# Acc_v0_1.net
KiCad netlist of a schematic drawn in EAGLE
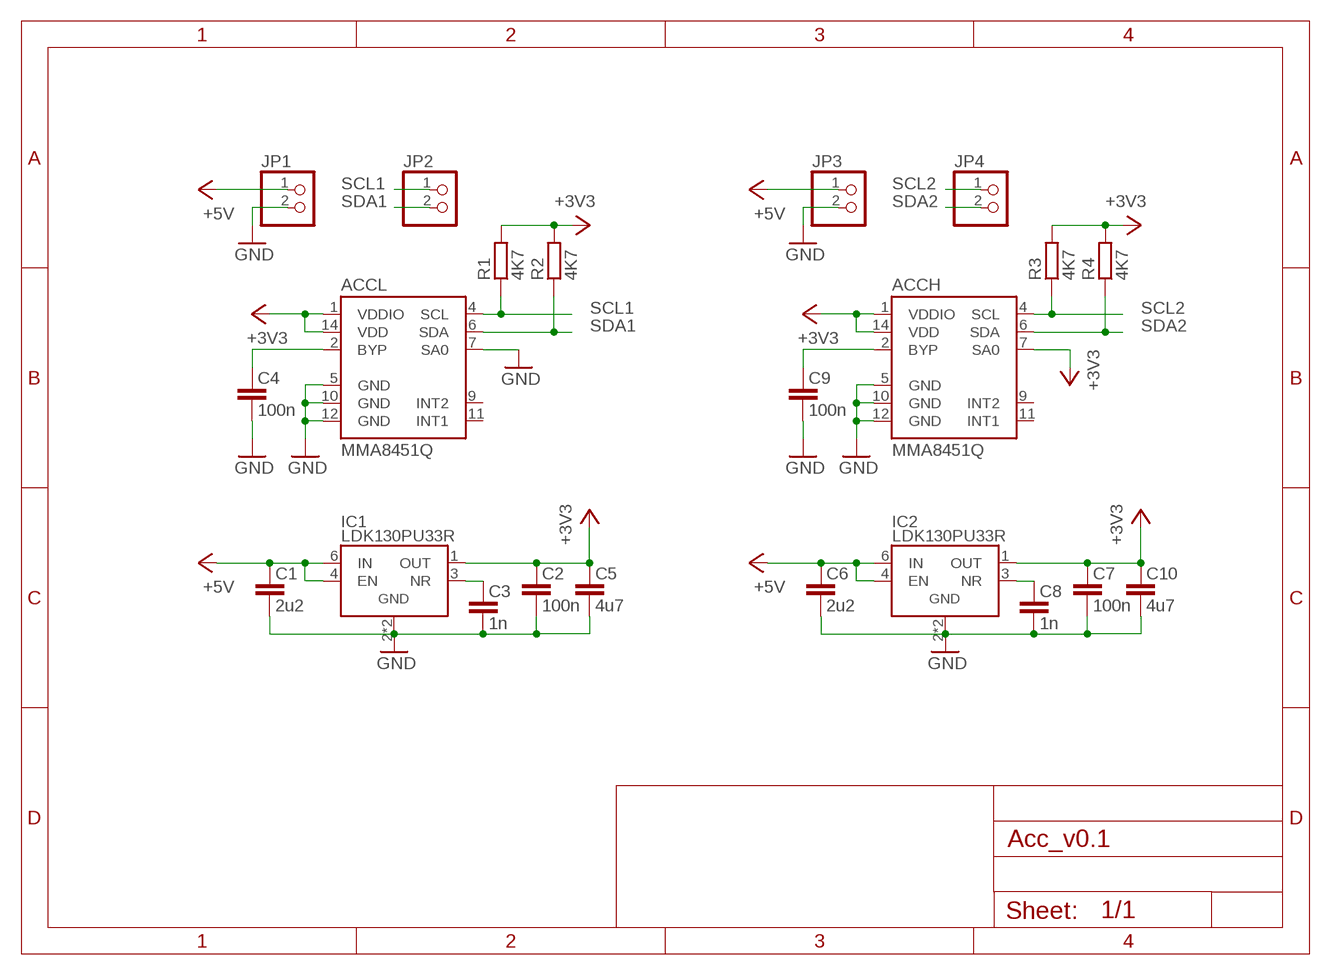
[diagram p0: schematic, sheet 1]

(export (version "E")
  (design (tool "Eeschema 10.0.6"))
  (components
    (comp (ref "ACCH")
      (value "MMA8451Q")
      (footprint "eagle-import:QFN-16")
      (libsource (lib "eagle-import") (part "MMA8451Q"))
    )
    (comp (ref "ACCL")
      (value "MMA8451Q")
      (footprint "eagle-import:QFN-16")
      (libsource (lib "eagle-import") (part "MMA8451Q"))
    )
    (comp (ref "C1")
      (value "2u2")
      (footprint "eagle-import:C0603G")
      (libsource (lib "eagle-import") (part "C_EU_C0603G"))
    )
    (comp (ref "C2")
      (value "100n")
      (footprint "eagle-import:C0603G")
      (libsource (lib "eagle-import") (part "C_EU_C0603G"))
    )
    (comp (ref "C3")
      (value "1n")
      (footprint "eagle-import:C0603G")
      (libsource (lib "eagle-import") (part "C_EU_C0603G"))
    )
    (comp (ref "C4")
      (value "100n")
      (footprint "eagle-import:C0603G")
      (libsource (lib "eagle-import") (part "C_EU_C0603G"))
    )
    (comp (ref "C5")
      (value "4u7")
      (footprint "eagle-import:C0603G")
      (libsource (lib "eagle-import") (part "C_EU_C0603G"))
    )
    (comp (ref "C6")
      (value "2u2")
      (footprint "eagle-import:C0603G")
      (libsource (lib "eagle-import") (part "C_EU_C0603G"))
    )
    (comp (ref "C7")
      (value "100n")
      (footprint "eagle-import:C0603G")
      (libsource (lib "eagle-import") (part "C_EU_C0603G"))
    )
    (comp (ref "C8")
      (value "1n")
      (footprint "eagle-import:C0603G")
      (libsource (lib "eagle-import") (part "C_EU_C0603G"))
    )
    (comp (ref "C9")
      (value "100n")
      (footprint "eagle-import:C0603G")
      (libsource (lib "eagle-import") (part "C_EU_C0603G"))
    )
    (comp (ref "C10")
      (value "4u7")
      (footprint "eagle-import:C0603G")
      (libsource (lib "eagle-import") (part "C_EU_C0603G"))
    )
    (comp (ref "IC1")
      (value "LDK130PU33R")
      (footprint "eagle-import:DFN6L")
      (libsource (lib "eagle-import") (part "LDK130PU33R"))
    )
    (comp (ref "IC2")
      (value "LDK130PU33R")
      (footprint "eagle-import:DFN6L")
      (libsource (lib "eagle-import") (part "LDK130PU33R"))
    )
    (comp (ref "JP1")
      (value "PINHD-1X2/SMD")
      (footprint "eagle-import:1X02S")
      (libsource (lib "eagle-import") (part "PINHD-1X2/SMD"))
    )
    (comp (ref "JP2")
      (value "PINHD-1X2/SMD")
      (footprint "eagle-import:1X02S")
      (libsource (lib "eagle-import") (part "PINHD-1X2/SMD"))
    )
    (comp (ref "JP3")
      (value "PINHD-1X2/SMD")
      (footprint "eagle-import:1X02S")
      (libsource (lib "eagle-import") (part "PINHD-1X2/SMD"))
    )
    (comp (ref "JP4")
      (value "PINHD-1X2/SMD")
      (footprint "eagle-import:1X02S")
      (libsource (lib "eagle-import") (part "PINHD-1X2/SMD"))
    )
    (comp (ref "R1")
      (value "4K7")
      (footprint "eagle-import:R0603")
      (libsource (lib "eagle-import") (part "R_EU_R0603"))
    )
    (comp (ref "R2")
      (value "4K7")
      (footprint "eagle-import:R0603")
      (libsource (lib "eagle-import") (part "R_EU_R0603"))
    )
    (comp (ref "R3")
      (value "4K7")
      (footprint "eagle-import:R0603")
      (libsource (lib "eagle-import") (part "R_EU_R0603"))
    )
    (comp (ref "R4")
      (value "4K7")
      (footprint "eagle-import:R0603")
      (libsource (lib "eagle-import") (part "R_EU_R0603"))
    )
  )
  (nets
    (net (code "1") (name "+3V3") (class "Default")
      (node (ref "ACCH") (pin "1") (pinfunction "VDDIO_1") (pintype "power_in"))
      (node (ref "ACCH") (pin "14") (pinfunction "VDD_14") (pintype "power_in"))
      (node (ref "ACCH") (pin "7") (pinfunction "SA0_7") (pintype "input"))
      (node (ref "ACCL") (pin "1") (pinfunction "VDDIO_1") (pintype "power_in"))
      (node (ref "ACCL") (pin "14") (pinfunction "VDD_14") (pintype "power_in"))
      (node (ref "C10") (pin "1") (pinfunction "1_1") (pintype "passive"))
      (node (ref "C2") (pin "1") (pinfunction "1_1") (pintype "passive"))
      (node (ref "C5") (pin "1") (pinfunction "1_1") (pintype "passive"))
      (node (ref "C7") (pin "1") (pinfunction "1_1") (pintype "passive"))
      (node (ref "IC1") (pin "1") (pinfunction "OUT_1") (pintype "power_in"))
      (node (ref "IC2") (pin "1") (pinfunction "OUT_1") (pintype "power_in"))
      (node (ref "R1") (pin "2") (pinfunction "2_2") (pintype "passive"))
      (node (ref "R2") (pin "2") (pinfunction "2_2") (pintype "passive"))
      (node (ref "R3") (pin "2") (pinfunction "2_2") (pintype "passive"))
      (node (ref "R4") (pin "2") (pinfunction "2_2") (pintype "passive"))
    )
    (net (code "2") (name "+5V") (class "Default")
      (node (ref "C1") (pin "1") (pinfunction "1_1") (pintype "passive"))
      (node (ref "C6") (pin "1") (pinfunction "1_1") (pintype "passive"))
      (node (ref "IC1") (pin "4") (pinfunction "EN_4") (pintype "passive"))
      (node (ref "IC1") (pin "6") (pinfunction "IN_6") (pintype "power_in"))
      (node (ref "IC2") (pin "4") (pinfunction "EN_4") (pintype "passive"))
      (node (ref "IC2") (pin "6") (pinfunction "IN_6") (pintype "power_in"))
      (node (ref "JP1") (pin "1") (pinfunction "1_1") (pintype "passive"))
      (node (ref "JP3") (pin "1") (pinfunction "1_1") (pintype "passive"))
    )
    (net (code "3") (name "/SCL1") (class "Default")
      (node (ref "ACCL") (pin "4") (pinfunction "SCL_4") (pintype "input"))
      (node (ref "JP2") (pin "1") (pinfunction "1_1") (pintype "passive"))
      (node (ref "R1") (pin "1") (pinfunction "1_1") (pintype "passive"))
    )
    (net (code "4") (name "/SCL2") (class "Default")
      (node (ref "ACCH") (pin "4") (pinfunction "SCL_4") (pintype "input"))
      (node (ref "JP4") (pin "1") (pinfunction "1_1") (pintype "passive"))
      (node (ref "R3") (pin "1") (pinfunction "1_1") (pintype "passive"))
    )
    (net (code "5") (name "/SDA1") (class "Default")
      (node (ref "ACCL") (pin "6") (pinfunction "SDA_6") (pintype "bidirectional"))
      (node (ref "JP2") (pin "2") (pinfunction "2_2") (pintype "passive"))
      (node (ref "R2") (pin "1") (pinfunction "1_1") (pintype "passive"))
    )
    (net (code "6") (name "/SDA2") (class "Default")
      (node (ref "ACCH") (pin "6") (pinfunction "SDA_6") (pintype "bidirectional"))
      (node (ref "JP4") (pin "2") (pinfunction "2_2") (pintype "passive"))
      (node (ref "R4") (pin "1") (pinfunction "1_1") (pintype "passive"))
    )
    (net (code "7") (name "GND") (class "Default")
      (node (ref "ACCH") (pin "10") (pinfunction "GND_10") (pintype "power_in"))
      (node (ref "ACCH") (pin "12") (pinfunction "GND_12") (pintype "power_in"))
      (node (ref "ACCH") (pin "5") (pinfunction "GND_5") (pintype "power_in"))
      (node (ref "ACCL") (pin "10") (pinfunction "GND_10") (pintype "power_in"))
      (node (ref "ACCL") (pin "12") (pinfunction "GND_12") (pintype "power_in"))
      (node (ref "ACCL") (pin "5") (pinfunction "GND_5") (pintype "power_in"))
      (node (ref "ACCL") (pin "7") (pinfunction "SA0_7") (pintype "input"))
      (node (ref "C1") (pin "2") (pinfunction "2_2") (pintype "passive"))
      (node (ref "C10") (pin "2") (pinfunction "2_2") (pintype "passive"))
      (node (ref "C2") (pin "2") (pinfunction "2_2") (pintype "passive"))
      (node (ref "C3") (pin "2") (pinfunction "2_2") (pintype "passive"))
      (node (ref "C4") (pin "2") (pinfunction "2_2") (pintype "passive"))
      (node (ref "C5") (pin "2") (pinfunction "2_2") (pintype "passive"))
      (node (ref "C6") (pin "2") (pinfunction "2_2") (pintype "passive"))
      (node (ref "C7") (pin "2") (pinfunction "2_2") (pintype "passive"))
      (node (ref "C8") (pin "2") (pinfunction "2_2") (pintype "passive"))
      (node (ref "C9") (pin "2") (pinfunction "2_2") (pintype "passive"))
      (node (ref "IC1") (pin "2") (pinfunction "GND_2") (pintype "power_in"))
      (node (ref "IC1") (pin "5") (pinfunction "GND_5") (pintype "power_in"))
      (node (ref "IC2") (pin "2") (pinfunction "GND_2") (pintype "power_in"))
      (node (ref "IC2") (pin "5") (pinfunction "GND_5") (pintype "power_in"))
      (node (ref "JP1") (pin "2") (pinfunction "2_2") (pintype "passive"))
      (node (ref "JP3") (pin "2") (pinfunction "2_2") (pintype "passive"))
    )
    (net (code "8") (name "Net-(ACCH-BYP)") (class "Default")
      (node (ref "ACCH") (pin "2") (pinfunction "BYP_2") (pintype "input"))
      (node (ref "C9") (pin "1") (pinfunction "1_1") (pintype "passive"))
    )
    (net (code "9") (name "Net-(ACCL-BYP)") (class "Default")
      (node (ref "ACCL") (pin "2") (pinfunction "BYP_2") (pintype "input"))
      (node (ref "C4") (pin "1") (pinfunction "1_1") (pintype "passive"))
    )
    (net (code "10") (name "Net-(IC1-NR)") (class "Default")
      (node (ref "C3") (pin "1") (pinfunction "1_1") (pintype "passive"))
      (node (ref "IC1") (pin "3") (pinfunction "NR_3") (pintype "passive"))
    )
    (net (code "11") (name "Net-(IC2-NR)") (class "Default")
      (node (ref "C8") (pin "1") (pinfunction "1_1") (pintype "passive"))
      (node (ref "IC2") (pin "3") (pinfunction "NR_3") (pintype "passive"))
    )
    (net (code "12") (name "unconnected-(ACCH-INT1-Pad11)") (class "Default")
      (node (ref "ACCH") (pin "11") (pinfunction "INT1_11") (pintype "output"))
    )
    (net (code "13") (name "unconnected-(ACCH-INT2-Pad9)") (class "Default")
      (node (ref "ACCH") (pin "9") (pinfunction "INT2_9") (pintype "output"))
    )
    (net (code "14") (name "unconnected-(ACCL-INT1-Pad11)") (class "Default")
      (node (ref "ACCL") (pin "11") (pinfunction "INT1_11") (pintype "output"))
    )
    (net (code "15") (name "unconnected-(ACCL-INT2-Pad9)") (class "Default")
      (node (ref "ACCL") (pin "9") (pinfunction "INT2_9") (pintype "output"))
    )
  )
)
